# myQT_nRF52840_Board.net
KiCad netlist of a schematic drawn in EAGLE
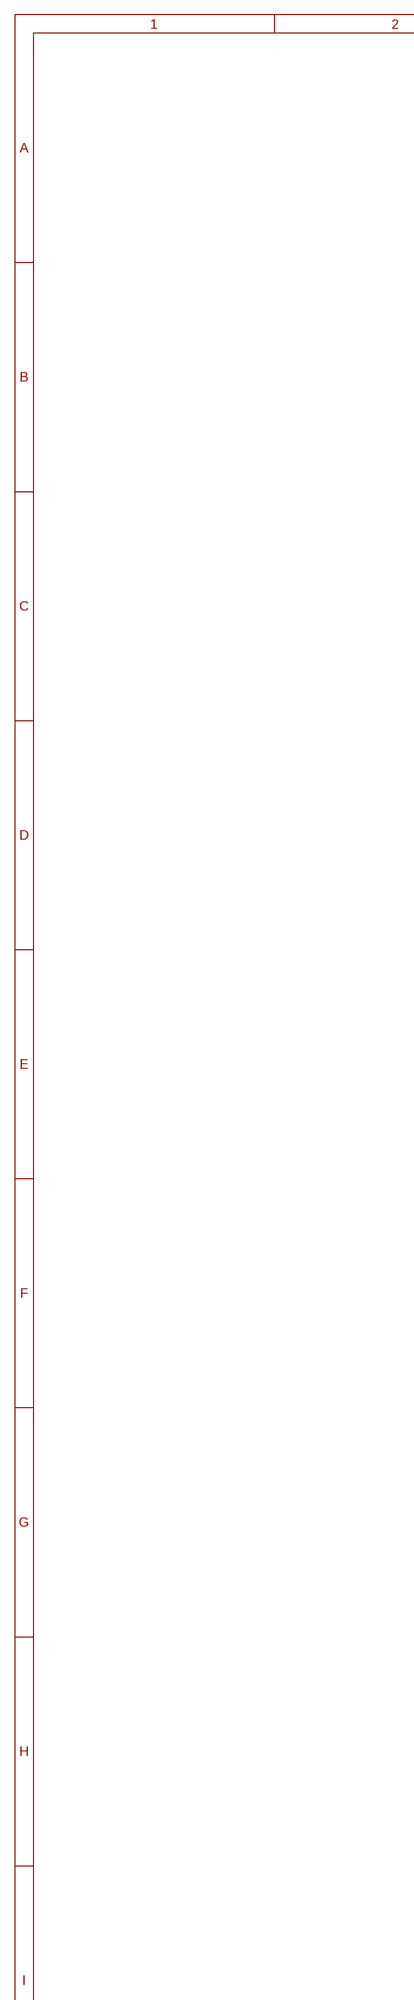
[diagram p0: schematic, sheet 1, part 1 of 2]
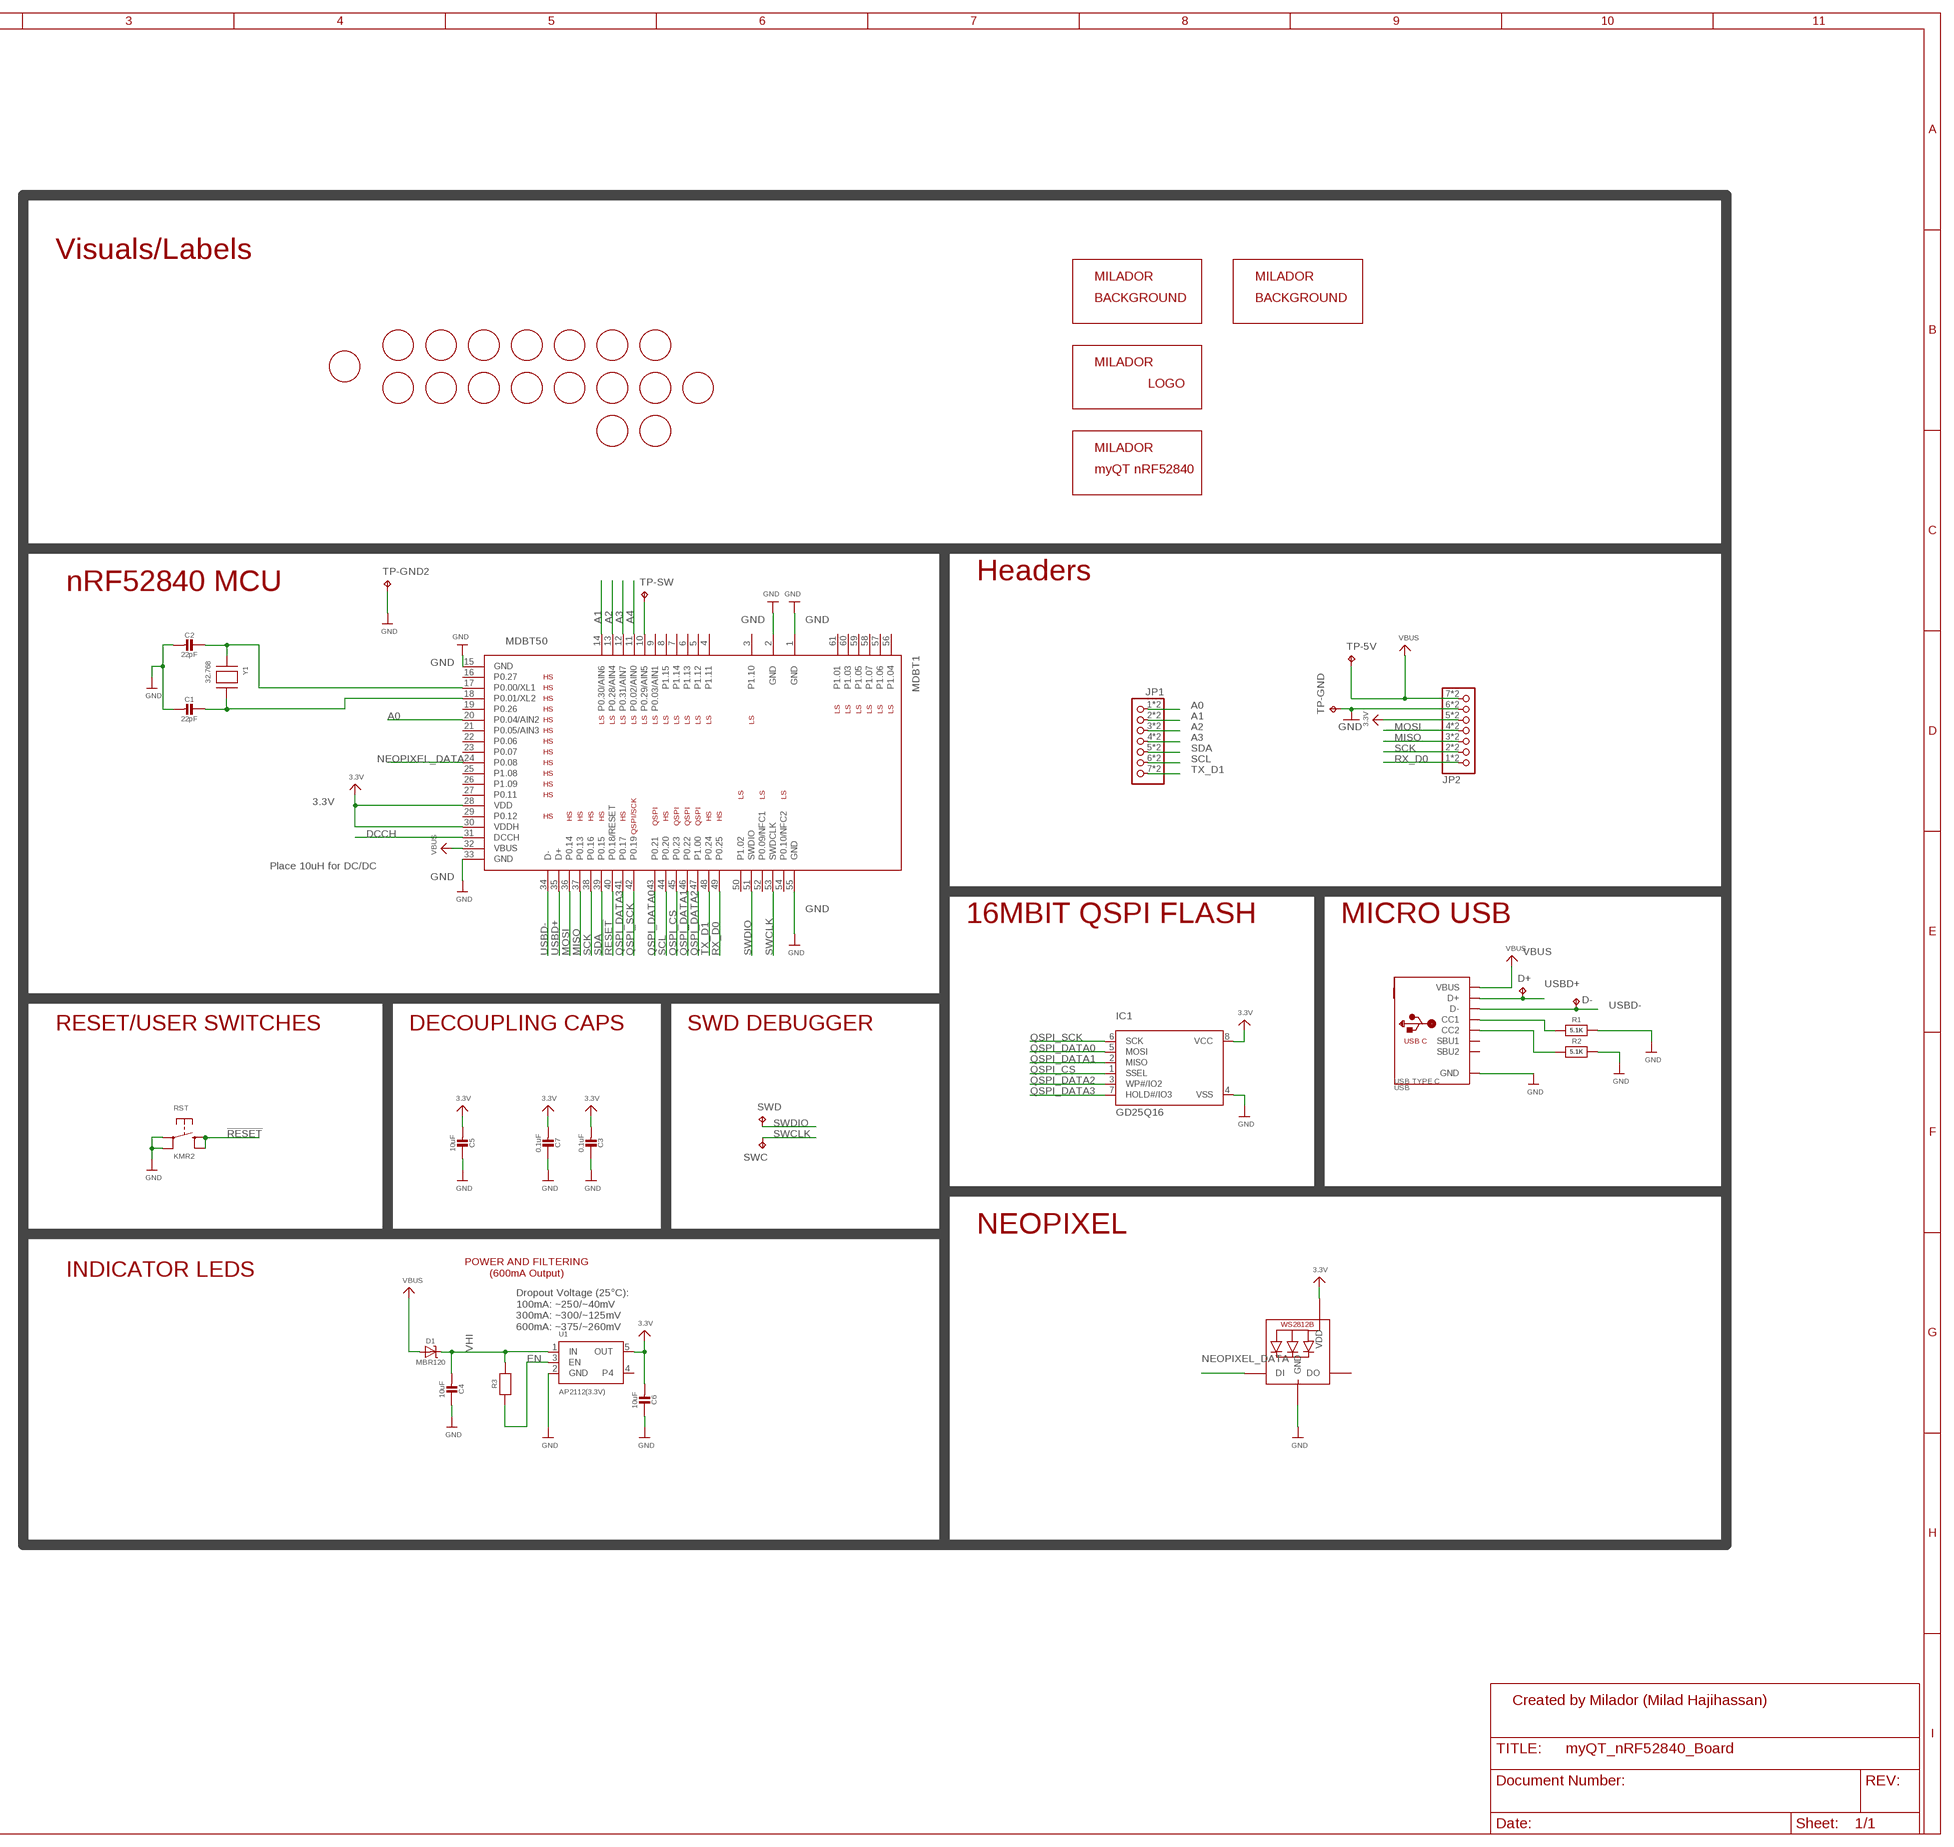
[diagram p1: schematic, sheet 1, part 2 of 2]

(export (version "E")
  (design (tool "Eeschema 10.0.6"))
  (components
    (comp (ref "C1")
      (value "22pF")
      (footprint "eagle-import:0603-MP")
      (libsource (lib "eagle-import") (part "CAP_CERAMIC-0603MP"))
    )
    (comp (ref "C2")
      (value "22pF")
      (footprint "eagle-import:0603-MP")
      (libsource (lib "eagle-import") (part "CAP_CERAMIC-0603MP"))
    )
    (comp (ref "C3")
      (value "0.1uF")
      (footprint "eagle-import:0603-NO")
      (libsource (lib "eagle-import") (part "CAP_CERAMIC-0603-NO"))
    )
    (comp (ref "C4")
      (value "10uF")
      (footprint "eagle-import:0805-NO")
      (libsource (lib "eagle-import") (part "CAP_CERAMIC-0805-NOOUTLINE"))
    )
    (comp (ref "C5")
      (value "10uF")
      (footprint "eagle-import:0805-NO")
      (libsource (lib "eagle-import") (part "CAP_CERAMIC-0805-NOOUTLINE"))
    )
    (comp (ref "C6")
      (value "10uF")
      (footprint "eagle-import:0805-NO")
      (libsource (lib "eagle-import") (part "CAP_CERAMIC-0805-NOOUTLINE"))
    )
    (comp (ref "C7")
      (value "0.1uF")
      (footprint "eagle-import:0603-NO")
      (libsource (lib "eagle-import") (part "CAP_CERAMIC-0603-NO"))
    )
    (comp (ref "D+")
      (value "TESTPAD_TPTP10R")
      (footprint "eagle-import:TESTPAD_TP10R")
      (libsource (lib "eagle-import") (part "TESTPAD_TPTP10R"))
    )
    (comp (ref "D-")
      (value "TESTPAD_TPTP10R")
      (footprint "eagle-import:TESTPAD_TP10R")
      (libsource (lib "eagle-import") (part "TESTPAD_TPTP10R"))
    )
    (comp (ref "D1")
      (value "MBR120")
      (footprint "eagle-import:SOD-123")
      (libsource (lib "eagle-import") (part "DIODE-SCHOTTKYSOD-123"))
    )
    (comp (ref "IC1")
      (value "GD25Q16")
      (footprint "eagle-import:USON8")
      (libsource (lib "eagle-import") (part "SPIFLASH_8PINUX"))
    )
    (comp (ref "JP1")
      (value "HEADER-1X7_CASTEL")
      (footprint "eagle-import:1X07_CASTEL")
      (libsource (lib "eagle-import") (part "HEADER-1X7_CASTEL"))
    )
    (comp (ref "JP2")
      (value "HEADER-1X7_CASTEL")
      (footprint "eagle-import:1X07_CASTEL")
      (libsource (lib "eagle-import") (part "HEADER-1X7_CASTEL"))
    )
    (comp (ref "LED")
      (value "WS2812B_SK6805_1515")
      (footprint "eagle-import:SK6805_1515")
      (libsource (lib "eagle-import") (part "WS2812B_SK6805_1515"))
    )
    (comp (ref "MDBT1")
      (value "MDBT50")
      (footprint "eagle-import:MDBT50")
      (libsource (lib "eagle-import") (part "MDBT50"))
    )
    (comp (ref "R1")
      (value "5.1K")
      (footprint "eagle-import:0402-NO")
      (libsource (lib "eagle-import") (part "RESISTOR-0402-NO"))
    )
    (comp (ref "R2")
      (value "5.1K")
      (footprint "eagle-import:0402-NO")
      (libsource (lib "eagle-import") (part "RESISTOR-0402-NO"))
    )
    (comp (ref "R3")
      (value "10K")
      (footprint "eagle-import:0603-NO")
      (libsource (lib "eagle-import") (part "RESISTOR-0603-NOOUT"))
    )
    (comp (ref "RST")
      (value "KMR2")
      (footprint "eagle-import:BTN_KMR2_4.6X2.8")
      (libsource (lib "eagle-import") (part "SWITCH_TACT_SMT4.6X2.8"))
    )
    (comp (ref "SWC")
      (value "TESTPAD_TPTP13R")
      (footprint "eagle-import:TESTPAD_TP13R")
      (libsource (lib "eagle-import") (part "TESTPAD_TPTP13R"))
    )
    (comp (ref "SWD")
      (value "TESTPAD_TPTP13R")
      (footprint "eagle-import:TESTPAD_TP13R")
      (libsource (lib "eagle-import") (part "TESTPAD_TPTP13R"))
    )
    (comp (ref "TP-5V")
      (value "TESTPAD_TPB1,27")
      (footprint "eagle-import:TESTPAD_B1,27")
      (libsource (lib "eagle-import") (part "TESTPAD_TPB1,27"))
    )
    (comp (ref "TP-GND")
      (value "TESTPAD_TPB1,27")
      (footprint "eagle-import:TESTPAD_B1,27")
      (libsource (lib "eagle-import") (part "TESTPAD_TPB1,27"))
    )
    (comp (ref "TP-GND2")
      (value "TESTPAD_TPTP06R")
      (footprint "eagle-import:TESTPAD_TP06R")
      (libsource (lib "eagle-import") (part "TESTPAD_TPTP06R"))
    )
    (comp (ref "TP-SW")
      (value "TESTPAD_TPTP06R")
      (footprint "eagle-import:TESTPAD_TP06R")
      (libsource (lib "eagle-import") (part "TESTPAD_TPTP06R"))
    )
    (comp (ref "U$6")
      (value "MILADOR-PIN-NAME-A0")
      (footprint "eagle-import:PIN-A0")
      (libsource (lib "eagle-import") (part "MILADOR-PIN-NAME-A0"))
    )
    (comp (ref "U$7")
      (value "MILADOR-PIN-NAME-5V")
      (footprint "eagle-import:PIN-5V")
      (libsource (lib "eagle-import") (part "MILADOR-PIN-NAME-5V"))
    )
    (comp (ref "U$10")
      (value "MILADOR-PIN-NAME-GND")
      (footprint "eagle-import:PIN-GND")
      (libsource (lib "eagle-import") (part "MILADOR-PIN-NAME-GND"))
    )
    (comp (ref "U$12")
      (value "MILADOR-PIN-NAME-3V")
      (footprint "eagle-import:PIN-3V")
      (libsource (lib "eagle-import") (part "MILADOR-PIN-NAME-3V"))
    )
    (comp (ref "U$14")
      (value "MILADOR-PIN-NAME-MO2")
      (footprint "eagle-import:PIN-MO2")
      (libsource (lib "eagle-import") (part "MILADOR-PIN-NAME-MO2"))
    )
    (comp (ref "U$18")
      (value "MILADOR-PIN-NAME-MI2")
      (footprint "eagle-import:PIN-MI2")
      (libsource (lib "eagle-import") (part "MILADOR-PIN-NAME-MI2"))
    )
    (comp (ref "U$20")
      (value "MILADOR-PIN-NAME-SCK2")
      (footprint "eagle-import:PIN-SCK2")
      (libsource (lib "eagle-import") (part "MILADOR-PIN-NAME-SCK2"))
    )
    (comp (ref "U$24")
      (value "MILADOR-PIN-NAME-RX")
      (footprint "eagle-import:PIN-RX")
      (libsource (lib "eagle-import") (part "MILADOR-PIN-NAME-RX"))
    )
    (comp (ref "U$25")
      (value "MILADOR-PIN-NAME-A1")
      (footprint "eagle-import:PIN-A1")
      (libsource (lib "eagle-import") (part "MILADOR-PIN-NAME-A1"))
    )
    (comp (ref "U$26")
      (value "MILADOR-PIN-NAME-A2")
      (footprint "eagle-import:PIN-A2")
      (libsource (lib "eagle-import") (part "MILADOR-PIN-NAME-A2"))
    )
    (comp (ref "U$27")
      (value "MILADOR-PIN-NAME-A3")
      (footprint "eagle-import:PIN-A3")
      (libsource (lib "eagle-import") (part "MILADOR-PIN-NAME-A3"))
    )
    (comp (ref "U$28")
      (value "MILADOR-PIN-NAME-TX")
      (footprint "eagle-import:PIN-TX")
      (libsource (lib "eagle-import") (part "MILADOR-PIN-NAME-TX"))
    )
    (comp (ref "U$29")
      (value "MILADOR-PIN-NAME-SDA2")
      (footprint "eagle-import:PIN-SDA2")
      (libsource (lib "eagle-import") (part "MILADOR-PIN-NAME-SDA2"))
    )
    (comp (ref "U$33")
      (value "MILADOR-PIN-NAME-SCL2")
      (footprint "eagle-import:PIN-SCL2")
      (libsource (lib "eagle-import") (part "MILADOR-PIN-NAME-SCL2"))
    )
    (comp (ref "U$36")
      (value "MILADOR-PIN-NAME-RST")
      (footprint "eagle-import:PIN-RST")
      (libsource (lib "eagle-import") (part "MILADOR-PIN-NAME-RST"))
    )
    (comp (ref "U$37")
      (value "MILADOR-BACKGROUND-VANCOUVER")
      (footprint "eagle-import:MILADOR_BG_VAN")
      (libsource (lib "eagle-import") (part "MILADOR-BACKGROUND-VANCOUVER"))
    )
    (comp (ref "U$38")
      (value "MILADOR-DEVICE-")
      (footprint "eagle-import:MILADOR_MYQT_NRF52840")
      (libsource (lib "eagle-import") (part "MILADOR-DEVICE-"))
    )
    (comp (ref "U$39")
      (value "MILADOR-LOGO-")
      (footprint "eagle-import:MILADOR_LOGO1")
      (libsource (lib "eagle-import") (part "MILADOR-LOGO-"))
    )
    (comp (ref "U$40")
      (value "MILADOR-BACKGROUND-CANADA_SM")
      (footprint "eagle-import:MILADOR_BG_CAN_SM")
      (libsource (lib "eagle-import") (part "MILADOR-BACKGROUND-CANADA_SM"))
    )
    (comp (ref "U$41")
      (value "MILADOR-PIN-NAME-D+")
      (footprint "eagle-import:PIN-D+")
      (libsource (lib "eagle-import") (part "MILADOR-PIN-NAME-D+"))
    )
    (comp (ref "U$43")
      (value "MILADOR-PIN-NAME-D-")
      (footprint "eagle-import:PIN-D-")
      (libsource (lib "eagle-import") (part "MILADOR-PIN-NAME-D-"))
    )
    (comp (ref "U$44")
      (value "MILADOR-PIN-NAME-SW")
      (footprint "eagle-import:PIN-SW")
      (libsource (lib "eagle-import") (part "MILADOR-PIN-NAME-SW"))
    )
    (comp (ref "U1")
      (value "AP2112(3.3V)")
      (footprint "eagle-import:SOT23-5")
      (libsource (lib "eagle-import") (part "VREG_SOT23-5"))
    )
    (comp (ref "USB")
      (value "USB TYPE C")
      (footprint "eagle-import:USB_C_CUSB31-CFM2AX-01-X")
      (libsource (lib "eagle-import") (part "USB_C"))
    )
    (comp (ref "Y1")
      (value "32.768")
      (footprint "eagle-import:ADAFRUIT2_XTAL3215")
      (libsource (lib "eagle-import") (part "ADAFRUIT2_XTAL-3.2X1.5"))
    )
  )
  (nets
    (net (code "1") (name "/A0") (class "Default")
      (node (ref "JP1") (pin "1") (pinfunction "1_1") (pintype "passive"))
      (node (ref "JP1") (pin "1C") (pinfunction "1_1C") (pintype "passive"))
      (node (ref "MDBT1") (pin "20") (pinfunction "P0.04/AIN2_20") (pintype "bidirectional"))
    )
    (net (code "2") (name "/A1") (class "Default")
      (node (ref "JP1") (pin "2") (pinfunction "2_2") (pintype "passive"))
      (node (ref "JP1") (pin "2C") (pinfunction "2_2C") (pintype "passive"))
      (node (ref "MDBT1") (pin "14") (pinfunction "P0.30/AIN6_14") (pintype "bidirectional"))
    )
    (net (code "3") (name "/A2") (class "Default")
      (node (ref "JP1") (pin "3") (pinfunction "3_3") (pintype "passive"))
      (node (ref "JP1") (pin "3C") (pinfunction "3_3C") (pintype "passive"))
      (node (ref "MDBT1") (pin "13") (pinfunction "P0.28/AIN4_13") (pintype "bidirectional"))
    )
    (net (code "4") (name "/A3") (class "Default")
      (node (ref "JP1") (pin "4") (pinfunction "4_4") (pintype "passive"))
      (node (ref "JP1") (pin "4C") (pinfunction "4_4C") (pintype "passive"))
      (node (ref "MDBT1") (pin "12") (pinfunction "P0.31/AIN7_12") (pintype "bidirectional"))
    )
    (net (code "5") (name "/A4") (class "Default")
      (node (ref "MDBT1") (pin "11") (pinfunction "P0.02/AIN0_11") (pintype "bidirectional"))
    )
    (net (code "6") (name "/DCCH") (class "Default")
      (node (ref "MDBT1") (pin "31") (pinfunction "DCCH_31") (pintype "bidirectional"))
    )
    (net (code "7") (name "/EN") (class "Default")
      (node (ref "R3") (pin "1") (pinfunction "1_1") (pintype "passive"))
      (node (ref "U1") (pin "3") (pinfunction "EN_3") (pintype "input"))
    )
    (net (code "8") (name "/MISO") (class "Default")
      (node (ref "JP2") (pin "3") (pinfunction "3_3") (pintype "passive"))
      (node (ref "JP2") (pin "3C") (pinfunction "3_3C") (pintype "passive"))
      (node (ref "MDBT1") (pin "37") (pinfunction "P0.13_37") (pintype "bidirectional"))
    )
    (net (code "9") (name "/MOSI") (class "Default")
      (node (ref "JP2") (pin "4") (pinfunction "4_4") (pintype "passive"))
      (node (ref "JP2") (pin "4C") (pinfunction "4_4C") (pintype "passive"))
      (node (ref "MDBT1") (pin "36") (pinfunction "P0.14_36") (pintype "bidirectional"))
    )
    (net (code "10") (name "/NEOPIXEL_DATA") (class "Default")
      (node (ref "LED") (pin "1") (pinfunction "DI_1") (pintype "input"))
      (node (ref "MDBT1") (pin "24") (pinfunction "P0.08_24") (pintype "bidirectional"))
    )
    (net (code "11") (name "/QSPI_CS") (class "Default")
      (node (ref "IC1") (pin "1") (pinfunction "SSEL_1") (pintype "bidirectional"))
      (node (ref "MDBT1") (pin "45") (pinfunction "P0.23_45") (pintype "bidirectional"))
    )
    (net (code "12") (name "/QSPI_DATA0") (class "Default")
      (node (ref "IC1") (pin "5") (pinfunction "MOSI_5") (pintype "bidirectional"))
      (node (ref "MDBT1") (pin "43") (pinfunction "P0.21_43") (pintype "bidirectional"))
    )
    (net (code "13") (name "/QSPI_DATA1") (class "Default")
      (node (ref "IC1") (pin "2") (pinfunction "MISO_2") (pintype "bidirectional"))
      (node (ref "MDBT1") (pin "46") (pinfunction "P0.22_46") (pintype "bidirectional"))
    )
    (net (code "14") (name "/QSPI_DATA2") (class "Default")
      (node (ref "IC1") (pin "3") (pinfunction "WP#/IO2_3") (pintype "bidirectional"))
      (node (ref "MDBT1") (pin "47") (pinfunction "P1.00_47") (pintype "bidirectional"))
    )
    (net (code "15") (name "/QSPI_DATA3") (class "Default")
      (node (ref "IC1") (pin "7") (pinfunction "HOLD#/IO3_7") (pintype "bidirectional"))
      (node (ref "MDBT1") (pin "41") (pinfunction "P0.17_41") (pintype "bidirectional"))
    )
    (net (code "16") (name "/QSPI_SCK") (class "Default")
      (node (ref "IC1") (pin "6") (pinfunction "SCK_6") (pintype "bidirectional"))
      (node (ref "MDBT1") (pin "42") (pinfunction "P0.19_42") (pintype "bidirectional"))
    )
    (net (code "17") (name "/RX_D0") (class "Default")
      (node (ref "JP2") (pin "1") (pinfunction "1_1") (pintype "passive"))
      (node (ref "JP2") (pin "1C") (pinfunction "1_1C") (pintype "passive"))
      (node (ref "MDBT1") (pin "49") (pinfunction "P0.25_49") (pintype "bidirectional"))
    )
    (net (code "18") (name "/SCK") (class "Default")
      (node (ref "JP2") (pin "2") (pinfunction "2_2") (pintype "passive"))
      (node (ref "JP2") (pin "2C") (pinfunction "2_2C") (pintype "passive"))
      (node (ref "MDBT1") (pin "38") (pinfunction "P0.16_38") (pintype "bidirectional"))
    )
    (net (code "19") (name "/SCL") (class "Default")
      (node (ref "JP1") (pin "6") (pinfunction "6_6") (pintype "passive"))
      (node (ref "JP1") (pin "6C") (pinfunction "6_6C") (pintype "passive"))
      (node (ref "MDBT1") (pin "44") (pinfunction "P0.20_44") (pintype "bidirectional"))
    )
    (net (code "20") (name "/SDA") (class "Default")
      (node (ref "JP1") (pin "5") (pinfunction "5_5") (pintype "passive"))
      (node (ref "JP1") (pin "5C") (pinfunction "5_5C") (pintype "passive"))
      (node (ref "MDBT1") (pin "39") (pinfunction "P0.15_39") (pintype "bidirectional"))
    )
    (net (code "21") (name "/SWCLK") (class "Default")
      (node (ref "MDBT1") (pin "53") (pinfunction "SWDCLK_53") (pintype "bidirectional"))
      (node (ref "SWC") (pin "TP") (pinfunction "TP_TP") (pintype "input"))
    )
    (net (code "22") (name "/SWDIO") (class "Default")
      (node (ref "MDBT1") (pin "51") (pinfunction "SWDIO_51") (pintype "bidirectional"))
      (node (ref "SWD") (pin "TP") (pinfunction "TP_TP") (pintype "input"))
    )
    (net (code "23") (name "/TX_D1") (class "Default")
      (node (ref "JP1") (pin "7") (pinfunction "7_7") (pintype "passive"))
      (node (ref "JP1") (pin "7C") (pinfunction "7_7C") (pintype "passive"))
      (node (ref "MDBT1") (pin "48") (pinfunction "P0.24_48") (pintype "bidirectional"))
    )
    (net (code "24") (name "/USBD+") (class "Default")
      (node (ref "D+") (pin "TP") (pinfunction "TP_TP") (pintype "input"))
      (node (ref "MDBT1") (pin "35") (pinfunction "D+_35") (pintype "bidirectional"))
      (node (ref "USB") (pin "A6") (pinfunction "D+_A6") (pintype "bidirectional"))
      (node (ref "USB") (pin "B6") (pinfunction "D+_B6") (pintype "bidirectional"))
    )
    (net (code "25") (name "/USBD-") (class "Default")
      (node (ref "D-") (pin "TP") (pinfunction "TP_TP") (pintype "input"))
      (node (ref "MDBT1") (pin "34") (pinfunction "D-_34") (pintype "bidirectional"))
      (node (ref "USB") (pin "A7") (pinfunction "D-_A7") (pintype "bidirectional"))
      (node (ref "USB") (pin "B7") (pinfunction "D-_B7") (pintype "bidirectional"))
    )
    (net (code "26") (name "/VHI") (class "Default")
      (node (ref "C4") (pin "2") (pinfunction "2_2") (pintype "passive"))
      (node (ref "D1") (pin "C") (pinfunction "C_C") (pintype "passive"))
      (node (ref "R3") (pin "2") (pinfunction "2_2") (pintype "passive"))
      (node (ref "U1") (pin "1") (pinfunction "IN_1") (pintype "power_in"))
    )
    (net (code "27") (name "/~{RESET}") (class "Default")
      (node (ref "MDBT1") (pin "40") (pinfunction "P0.18/RESET_40") (pintype "bidirectional"))
      (node (ref "RST") (pin "B") (pinfunction "S_B") (pintype "passive"))
      (node (ref "RST") (pin "B'") (pinfunction "S1_B'") (pintype "passive"))
    )
    (net (code "28") (name "3.3V") (class "Default")
      (node (ref "C3") (pin "2") (pinfunction "2_2") (pintype "passive"))
      (node (ref "C5") (pin "2") (pinfunction "2_2") (pintype "passive"))
      (node (ref "C6") (pin "2") (pinfunction "2_2") (pintype "passive"))
      (node (ref "C7") (pin "2") (pinfunction "2_2") (pintype "passive"))
      (node (ref "IC1") (pin "8") (pinfunction "VCC_8") (pintype "bidirectional"))
      (node (ref "JP2") (pin "5") (pinfunction "5_5") (pintype "passive"))
      (node (ref "JP2") (pin "5C") (pinfunction "5_5C") (pintype "passive"))
      (node (ref "LED") (pin "2") (pinfunction "VDD_2") (pintype "power_in"))
      (node (ref "MDBT1") (pin "28") (pinfunction "VDD_28") (pintype "bidirectional"))
      (node (ref "MDBT1") (pin "30") (pinfunction "VDDH_30") (pintype "bidirectional"))
      (node (ref "U1") (pin "5") (pinfunction "OUT_5") (pintype "power_in"))
    )
    (net (code "29") (name "GND") (class "Default")
      (node (ref "C1") (pin "2") (pinfunction "2_2") (pintype "passive"))
      (node (ref "C2") (pin "2") (pinfunction "2_2") (pintype "passive"))
      (node (ref "C3") (pin "1") (pinfunction "1_1") (pintype "passive"))
      (node (ref "C4") (pin "1") (pinfunction "1_1") (pintype "passive"))
      (node (ref "C5") (pin "1") (pinfunction "1_1") (pintype "passive"))
      (node (ref "C6") (pin "1") (pinfunction "1_1") (pintype "passive"))
      (node (ref "C7") (pin "1") (pinfunction "1_1") (pintype "passive"))
      (node (ref "IC1") (pin "4") (pinfunction "VSS_4") (pintype "bidirectional"))
      (node (ref "JP2") (pin "6") (pinfunction "6_6") (pintype "passive"))
      (node (ref "JP2") (pin "6C") (pinfunction "6_6C") (pintype "passive"))
      (node (ref "LED") (pin "4") (pinfunction "GND_4") (pintype "power_in"))
      (node (ref "MDBT1") (pin "1") (pinfunction "GND_1") (pintype "bidirectional"))
      (node (ref "MDBT1") (pin "15") (pinfunction "GND_15") (pintype "bidirectional"))
      (node (ref "MDBT1") (pin "2") (pinfunction "GND_2") (pintype "bidirectional"))
      (node (ref "MDBT1") (pin "33") (pinfunction "GND_33") (pintype "bidirectional"))
      (node (ref "MDBT1") (pin "55") (pinfunction "GND_55") (pintype "bidirectional"))
      (node (ref "R1") (pin "2") (pinfunction "2_2") (pintype "passive"))
      (node (ref "R2") (pin "2") (pinfunction "2_2") (pintype "passive"))
      (node (ref "RST") (pin "A") (pinfunction "P_A") (pintype "passive"))
      (node (ref "RST") (pin "A'") (pinfunction "P1_A'") (pintype "passive"))
      (node (ref "TP-GND") (pin "TP") (pinfunction "TP_TP") (pintype "input"))
      (node (ref "TP-GND2") (pin "TP") (pinfunction "TP_TP") (pintype "input"))
      (node (ref "U1") (pin "2") (pinfunction "GND_2") (pintype "power_in"))
      (node (ref "USB") (pin "A1B12") (pinfunction "GND_A1B12") (pintype "power_in"))
      (node (ref "USB") (pin "B1A12") (pinfunction "GND_B1A12") (pintype "power_in"))
    )
    (net (code "30") (name "Net-(MDBT1-P0.00{slash}XL1)") (class "Default")
      (node (ref "C2") (pin "1") (pinfunction "1_1") (pintype "passive"))
      (node (ref "MDBT1") (pin "17") (pinfunction "P0.00/XL1_17") (pintype "bidirectional"))
      (node (ref "Y1") (pin "P$1") (pinfunction "P$1_P$1") (pintype "bidirectional"))
    )
    (net (code "31") (name "Net-(MDBT1-P0.01{slash}XL2)") (class "Default")
      (node (ref "C1") (pin "1") (pinfunction "1_1") (pintype "passive"))
      (node (ref "MDBT1") (pin "18") (pinfunction "P0.01/XL2_18") (pintype "bidirectional"))
      (node (ref "Y1") (pin "P$2") (pinfunction "P$2_P$2") (pintype "bidirectional"))
    )
    (net (code "32") (name "Net-(MDBT1-P0.29{slash}AIN5)") (class "Default")
      (node (ref "MDBT1") (pin "10") (pinfunction "P0.29/AIN5_10") (pintype "bidirectional"))
      (node (ref "TP-SW") (pin "TP") (pinfunction "TP_TP") (pintype "input"))
    )
    (net (code "33") (name "Net-(USB-CC1)") (class "Default")
      (node (ref "R1") (pin "1") (pinfunction "1_1") (pintype "passive"))
      (node (ref "USB") (pin "A5") (pinfunction "CC1_A5") (pintype "bidirectional"))
    )
    (net (code "34") (name "Net-(USB-CC2)") (class "Default")
      (node (ref "R2") (pin "1") (pinfunction "1_1") (pintype "passive"))
      (node (ref "USB") (pin "B5") (pinfunction "CC2_B5") (pintype "bidirectional"))
    )
    (net (code "35") (name "VBUS") (class "Default")
      (node (ref "D1") (pin "A") (pinfunction "A_A") (pintype "passive"))
      (node (ref "JP2") (pin "7") (pinfunction "7_7") (pintype "passive"))
      (node (ref "JP2") (pin "7C") (pinfunction "7_7C") (pintype "passive"))
      (node (ref "MDBT1") (pin "32") (pinfunction "VBUS_32") (pintype "bidirectional"))
      (node (ref "TP-5V") (pin "TP") (pinfunction "TP_TP") (pintype "input"))
      (node (ref "USB") (pin "A4B9") (pinfunction "VBUS_A4B9") (pintype "power_in"))
      (node (ref "USB") (pin "B4A9") (pinfunction "VBUS_B4A9") (pintype "power_in"))
    )
    (net (code "36") (name "unconnected-(LED-DO-Pad3)") (class "Default")
      (node (ref "LED") (pin "3") (pinfunction "DO_3") (pintype "output"))
    )
    (net (code "37") (name "unconnected-(MDBT1-P0.03{slash}AIN1-Pad9)") (class "Default")
      (node (ref "MDBT1") (pin "9") (pinfunction "P0.03/AIN1_9") (pintype "bidirectional"))
    )
    (net (code "38") (name "unconnected-(MDBT1-P0.05{slash}AIN3-Pad21)") (class "Default")
      (node (ref "MDBT1") (pin "21") (pinfunction "P0.05/AIN3_21") (pintype "bidirectional"))
    )
    (net (code "39") (name "unconnected-(MDBT1-P0.06-Pad22)") (class "Default")
      (node (ref "MDBT1") (pin "22") (pinfunction "P0.06_22") (pintype "bidirectional"))
    )
    (net (code "40") (name "unconnected-(MDBT1-P0.07-Pad23)") (class "Default")
      (node (ref "MDBT1") (pin "23") (pinfunction "P0.07_23") (pintype "bidirectional"))
    )
    (net (code "41") (name "unconnected-(MDBT1-P0.09{slash}NFC1-Pad52)") (class "Default")
      (node (ref "MDBT1") (pin "52") (pinfunction "P0.09/NFC1_52") (pintype "bidirectional"))
    )
    (net (code "42") (name "unconnected-(MDBT1-P0.10{slash}NFC2-Pad54)") (class "Default")
      (node (ref "MDBT1") (pin "54") (pinfunction "P0.10/NFC2_54") (pintype "bidirectional"))
    )
    (net (code "43") (name "unconnected-(MDBT1-P0.11-Pad27)") (class "Default")
      (node (ref "MDBT1") (pin "27") (pinfunction "P0.11_27") (pintype "bidirectional"))
    )
    (net (code "44") (name "unconnected-(MDBT1-P0.12-Pad29)") (class "Default")
      (node (ref "MDBT1") (pin "29") (pinfunction "P0.12_29") (pintype "bidirectional"))
    )
    (net (code "45") (name "unconnected-(MDBT1-P0.26-Pad19)") (class "Default")
      (node (ref "MDBT1") (pin "19") (pinfunction "P0.26_19") (pintype "bidirectional"))
    )
    (net (code "46") (name "unconnected-(MDBT1-P0.27-Pad16)") (class "Default")
      (node (ref "MDBT1") (pin "16") (pinfunction "P0.27_16") (pintype "bidirectional"))
    )
    (net (code "47") (name "unconnected-(MDBT1-P1.01-Pad61)") (class "Default")
      (node (ref "MDBT1") (pin "61") (pinfunction "P1.01_61") (pintype "bidirectional"))
    )
    (net (code "48") (name "unconnected-(MDBT1-P1.02-Pad50)") (class "Default")
      (node (ref "MDBT1") (pin "50") (pinfunction "P1.02_50") (pintype "bidirectional"))
    )
    (net (code "49") (name "unconnected-(MDBT1-P1.03-Pad60)") (class "Default")
      (node (ref "MDBT1") (pin "60") (pinfunction "P1.03_60") (pintype "bidirectional"))
    )
    (net (code "50") (name "unconnected-(MDBT1-P1.04-Pad56)") (class "Default")
      (node (ref "MDBT1") (pin "56") (pinfunction "P1.04_56") (pintype "bidirectional"))
    )
    (net (code "51") (name "unconnected-(MDBT1-P1.05-Pad59)") (class "Default")
      (node (ref "MDBT1") (pin "59") (pinfunction "P1.05_59") (pintype "bidirectional"))
    )
    (net (code "52") (name "unconnected-(MDBT1-P1.06-Pad57)") (class "Default")
      (node (ref "MDBT1") (pin "57") (pinfunction "P1.06_57") (pintype "bidirectional"))
    )
    (net (code "53") (name "unconnected-(MDBT1-P1.07-Pad58)") (class "Default")
      (node (ref "MDBT1") (pin "58") (pinfunction "P1.07_58") (pintype "bidirectional"))
    )
    (net (code "54") (name "unconnected-(MDBT1-P1.08-Pad25)") (class "Default")
      (node (ref "MDBT1") (pin "25") (pinfunction "P1.08_25") (pintype "bidirectional"))
    )
    (net (code "55") (name "unconnected-(MDBT1-P1.09-Pad26)") (class "Default")
      (node (ref "MDBT1") (pin "26") (pinfunction "P1.09_26") (pintype "bidirectional"))
    )
    (net (code "56") (name "unconnected-(MDBT1-P1.10-Pad3)") (class "Default")
      (node (ref "MDBT1") (pin "3") (pinfunction "P1.10_3") (pintype "bidirectional"))
    )
    (net (code "57") (name "unconnected-(MDBT1-P1.11-Pad4)") (class "Default")
      (node (ref "MDBT1") (pin "4") (pinfunction "P1.11_4") (pintype "bidirectional"))
    )
    (net (code "58") (name "unconnected-(MDBT1-P1.12-Pad5)") (class "Default")
      (node (ref "MDBT1") (pin "5") (pinfunction "P1.12_5") (pintype "bidirectional"))
    )
    (net (code "59") (name "unconnected-(MDBT1-P1.13-Pad6)") (class "Default")
      (node (ref "MDBT1") (pin "6") (pinfunction "P1.13_6") (pintype "bidirectional"))
    )
    (net (code "60") (name "unconnected-(MDBT1-P1.14-Pad7)") (class "Default")
      (node (ref "MDBT1") (pin "7") (pinfunction "P1.14_7") (pintype "bidirectional"))
    )
    (net (code "61") (name "unconnected-(MDBT1-P1.15-Pad8)") (class "Default")
      (node (ref "MDBT1") (pin "8") (pinfunction "P1.15_8") (pintype "bidirectional"))
    )
    (net (code "62") (name "unconnected-(U1-P4-Pad4)") (class "Default")
      (node (ref "U1") (pin "4") (pinfunction "P4_4") (pintype "bidirectional"))
    )
    (net (code "63") (name "unconnected-(USB-SBU1-PadA8)") (class "Default")
      (node (ref "USB") (pin "A8") (pinfunction "SBU1_A8") (pintype "bidirectional"))
    )
    (net (code "64") (name "unconnected-(USB-SBU2-PadB8)") (class "Default")
      (node (ref "USB") (pin "B8") (pinfunction "SBU2_B8") (pintype "bidirectional"))
    )
  )
)
